# Schematic1.net
KiCad netlist of a schematic drawn in EAGLE
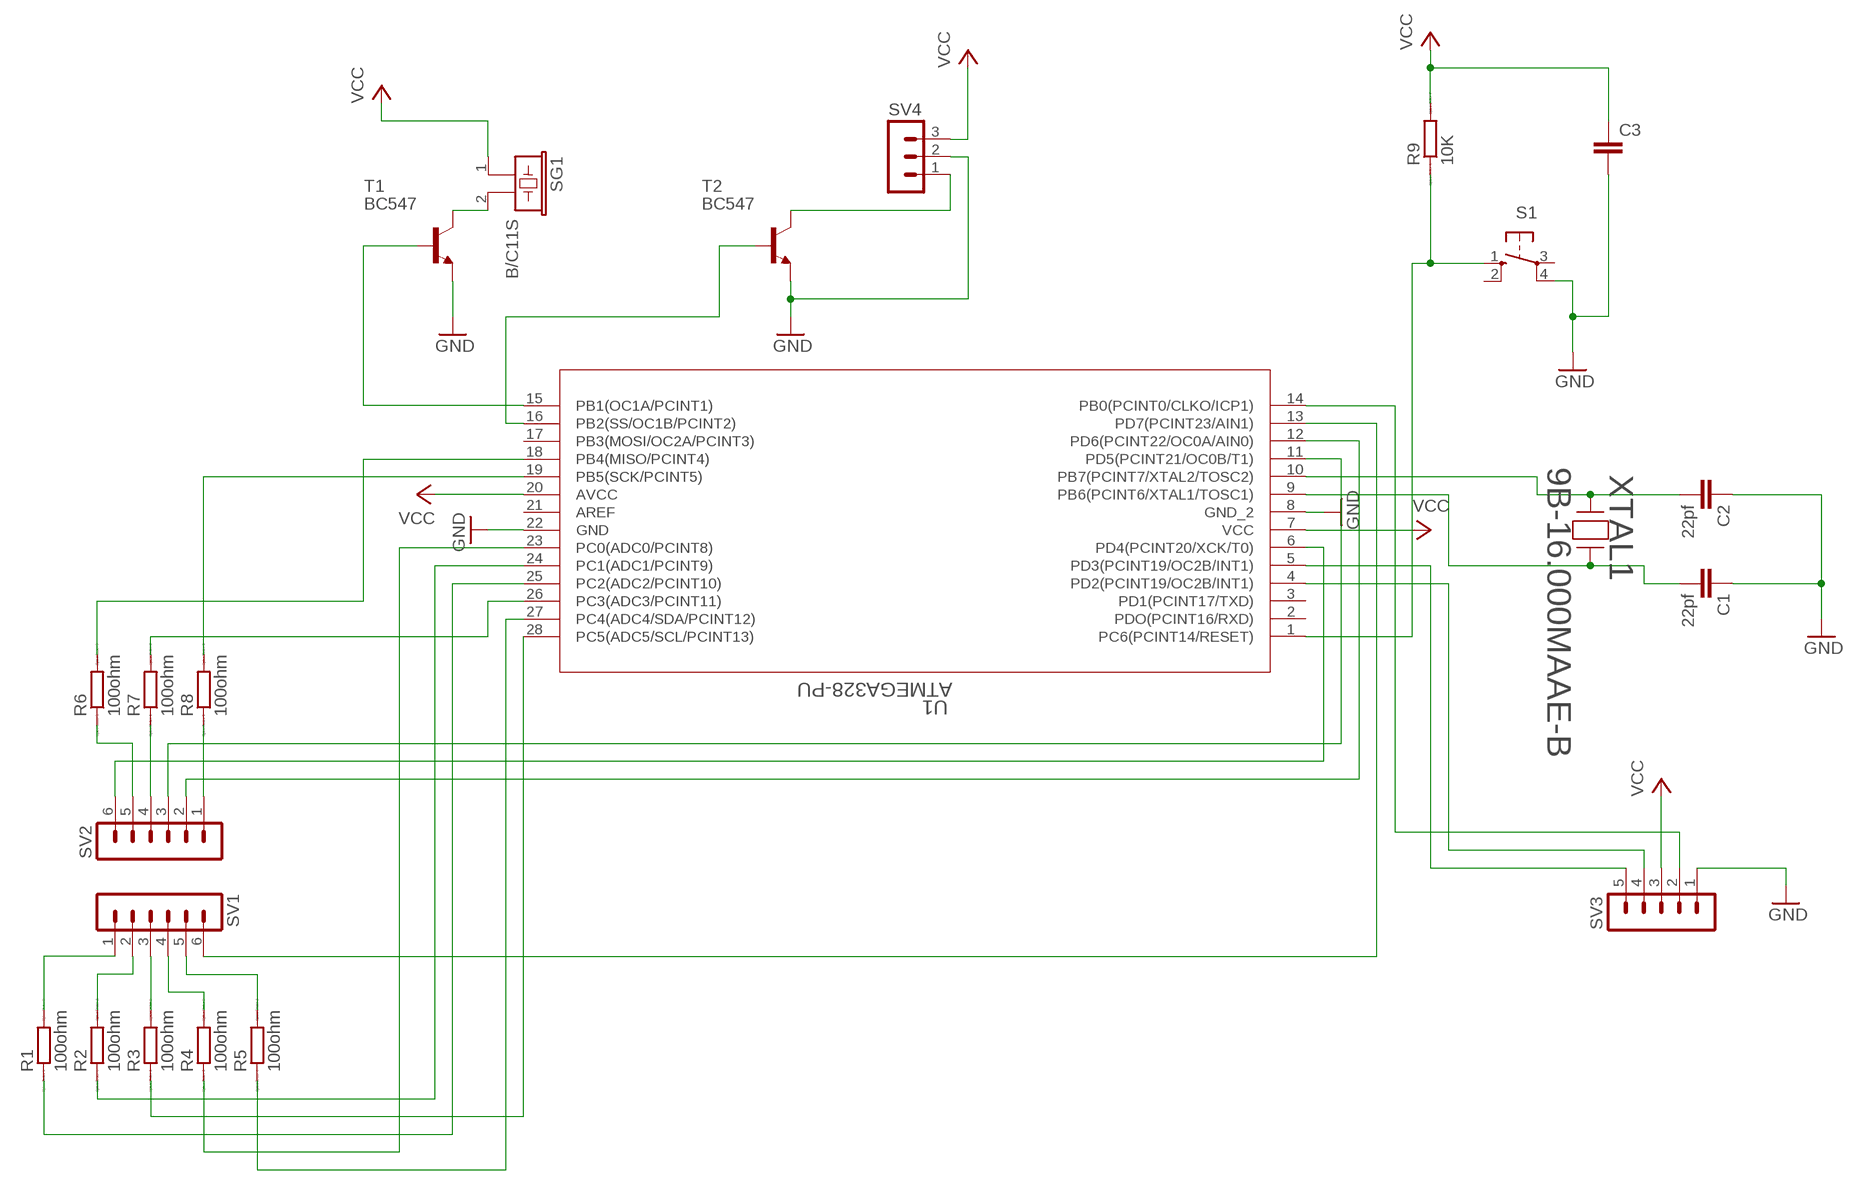
[diagram p0: schematic, sheet 1]

(export (version "E")
  (design (tool "Eeschema 10.0.6"))
  (components
    (comp (ref "C1")
      (value "22pf")
      (footprint "eagle-import:C2.5-3")
      (libsource (lib "eagle-import") (part "C2,5-3"))
    )
    (comp (ref "C2")
      (value "22pf")
      (footprint "eagle-import:C2.5-3")
      (libsource (lib "eagle-import") (part "C2,5-3"))
    )
    (comp (ref "C3")
      (value "C5/3")
      (footprint "eagle-import:C5B3")
      (libsource (lib "eagle-import") (part "C5/3"))
    )
    (comp (ref "R1")
      (value "100ohm")
      (footprint "eagle-import:0204_7")
      (libsource (lib "eagle-import") (part "R0204/7"))
    )
    (comp (ref "R2")
      (value "100ohm")
      (footprint "eagle-import:0204_7")
      (libsource (lib "eagle-import") (part "R0204/7"))
    )
    (comp (ref "R3")
      (value "100ohm")
      (footprint "eagle-import:0204_7")
      (libsource (lib "eagle-import") (part "R0204/7"))
    )
    (comp (ref "R4")
      (value "100ohm")
      (footprint "eagle-import:0204_7")
      (libsource (lib "eagle-import") (part "R0204/7"))
    )
    (comp (ref "R5")
      (value "100ohm")
      (footprint "eagle-import:0204_7")
      (libsource (lib "eagle-import") (part "R0204/7"))
    )
    (comp (ref "R6")
      (value "100ohm")
      (footprint "eagle-import:0204_7")
      (libsource (lib "eagle-import") (part "R0204/7"))
    )
    (comp (ref "R7")
      (value "100ohm")
      (footprint "eagle-import:0204_7")
      (libsource (lib "eagle-import") (part "R0204/7"))
    )
    (comp (ref "R8")
      (value "100ohm")
      (footprint "eagle-import:0204_7")
      (libsource (lib "eagle-import") (part "R0204/7"))
    )
    (comp (ref "R9")
      (value "10K")
      (footprint "eagle-import:0204_7")
      (libsource (lib "eagle-import") (part "R0204/7"))
    )
    (comp (ref "S1")
      (value "10-XX")
      (footprint "eagle-import:B3F-10XX")
      (fields (field (name "MPN") "B3F-1000"))
      (libsource (lib "eagle-import") (part "10-XX"))
    )
    (comp (ref "SG1")
      (value "B/C11S")
      (footprint "eagle-import:B_C11S")
      (libsource (lib "eagle-import") (part "B/C11S"))
    )
    (comp (ref "SV1")
      (value "MA06-1")
      (footprint "eagle-import:MA06-1")
      (libsource (lib "eagle-import") (part "MA06-1"))
    )
    (comp (ref "SV2")
      (value "MA06-1")
      (footprint "eagle-import:MA06-1")
      (libsource (lib "eagle-import") (part "MA06-1"))
    )
    (comp (ref "SV3")
      (value "MA05-1")
      (footprint "eagle-import:MA05-1")
      (libsource (lib "eagle-import") (part "MA05-1"))
    )
    (comp (ref "SV4")
      (value "MA03-1")
      (footprint "eagle-import:MA03-1")
      (libsource (lib "eagle-import") (part "MA03-1"))
    )
    (comp (ref "T1")
      (value "BC547")
      (footprint "eagle-import:TO92")
      (libsource (lib "eagle-import") (part "BC547"))
    )
    (comp (ref "T2")
      (value "BC547")
      (footprint "eagle-import:TO92")
      (libsource (lib "eagle-import") (part "BC547"))
    )
    (comp (ref "U1")
      (value "ATMEGA328-PU")
      (footprint "eagle-import:28P3_SPDIP28_SP_MCH")
      (fields (field (name "COPYRIGHT") "Copyright (C) 2023 Ultra Librarian. All rights reserved."))
      (libsource (lib "eagle-import") (part "ATMEGA328-PU"))
    )
    (comp (ref "XTAL1")
      (value "9B-16.000MAAE-B")
      (footprint "eagle-import:9B-16.000MAAE-B_TXC")
      (fields (field (name "COPYRIGHT") "Copyright (C) 2023 Ultra Librarian. All rights reserved."))
      (libsource (lib "eagle-import") (part "9B-16.000MAAE-B"))
    )
  )
  (nets
    (net (code "1") (name "GND") (class "Default")
      (node (ref "C1") (pin "1") (pinfunction "1_1") (pintype "passive"))
      (node (ref "C2") (pin "1") (pinfunction "1_1") (pintype "passive"))
      (node (ref "C3") (pin "2") (pinfunction "2_2") (pintype "passive"))
      (node (ref "S1") (pin "4") (pinfunction "P1_4") (pintype "passive"))
      (node (ref "SV3") (pin "1") (pinfunction "1_1") (pintype "passive"))
      (node (ref "SV4") (pin "2") (pinfunction "2_2") (pintype "passive"))
      (node (ref "T1") (pin "1") (pinfunction "E_1") (pintype "passive"))
      (node (ref "T2") (pin "1") (pinfunction "E_1") (pintype "passive"))
      (node (ref "U1") (pin "22") (pinfunction "GND_22") (pintype "passive"))
      (node (ref "U1") (pin "8") (pinfunction "GND_2_8") (pintype "passive"))
    )
    (net (code "2") (name "Net-(R1-Pad2)") (class "Default")
      (node (ref "R1") (pin "2") (pinfunction "2_2") (pintype "passive"))
      (node (ref "SV1") (pin "1") (pinfunction "1_1") (pintype "passive"))
    )
    (net (code "3") (name "Net-(R2-Pad2)") (class "Default")
      (node (ref "R2") (pin "2") (pinfunction "2_2") (pintype "passive"))
      (node (ref "SV1") (pin "2") (pinfunction "2_2") (pintype "passive"))
    )
    (net (code "4") (name "Net-(R3-Pad2)") (class "Default")
      (node (ref "R3") (pin "2") (pinfunction "2_2") (pintype "passive"))
      (node (ref "SV1") (pin "3") (pinfunction "3_3") (pintype "passive"))
    )
    (net (code "5") (name "Net-(R4-Pad2)") (class "Default")
      (node (ref "R4") (pin "2") (pinfunction "2_2") (pintype "passive"))
      (node (ref "SV1") (pin "4") (pinfunction "4_4") (pintype "passive"))
    )
    (net (code "6") (name "Net-(R5-Pad2)") (class "Default")
      (node (ref "R5") (pin "2") (pinfunction "2_2") (pintype "passive"))
      (node (ref "SV1") (pin "5") (pinfunction "5_5") (pintype "passive"))
    )
    (net (code "7") (name "Net-(R6-Pad1)") (class "Default")
      (node (ref "R6") (pin "1") (pinfunction "1_1") (pintype "passive"))
      (node (ref "SV2") (pin "5") (pinfunction "5_5") (pintype "passive"))
    )
    (net (code "8") (name "Net-(R7-Pad1)") (class "Default")
      (node (ref "R7") (pin "1") (pinfunction "1_1") (pintype "passive"))
      (node (ref "SV2") (pin "4") (pinfunction "4_4") (pintype "passive"))
    )
    (net (code "9") (name "Net-(R8-Pad1)") (class "Default")
      (node (ref "R8") (pin "1") (pinfunction "1_1") (pintype "passive"))
      (node (ref "SV2") (pin "1") (pinfunction "1_1") (pintype "passive"))
    )
    (net (code "10") (name "Net-(S1-S)") (class "Default")
      (node (ref "R9") (pin "1") (pinfunction "1_1") (pintype "passive"))
      (node (ref "S1") (pin "1") (pinfunction "S_1") (pintype "passive"))
      (node (ref "U1") (pin "1") (pinfunction "PC6(PCINT14/RESET)_1") (pintype "bidirectional"))
    )
    (net (code "11") (name "Net-(T1-B)") (class "Default")
      (node (ref "T1") (pin "2") (pinfunction "B_2") (pintype "passive"))
      (node (ref "U1") (pin "15") (pinfunction "PB1(OC1A/PCINT1)_15") (pintype "bidirectional"))
    )
    (net (code "12") (name "Net-(T1-C)") (class "Default")
      (node (ref "SG1") (pin "2") (pinfunction "2_2") (pintype "passive"))
      (node (ref "T1") (pin "3") (pinfunction "C_3") (pintype "passive"))
    )
    (net (code "13") (name "Net-(T2-B)") (class "Default")
      (node (ref "T2") (pin "2") (pinfunction "B_2") (pintype "passive"))
      (node (ref "U1") (pin "16") (pinfunction "PB2(SS/OC1B/PCINT2)_16") (pintype "bidirectional"))
    )
    (net (code "14") (name "Net-(T2-C)") (class "Default")
      (node (ref "SV4") (pin "1") (pinfunction "1_1") (pintype "passive"))
      (node (ref "T2") (pin "3") (pinfunction "C_3") (pintype "passive"))
    )
    (net (code "15") (name "Net-(U1-PB0(PCINT0{slash}CLKO{slash}ICP1))") (class "Default")
      (node (ref "SV3") (pin "2") (pinfunction "2_2") (pintype "passive"))
      (node (ref "SV3") (pin "5") (pinfunction "5_5") (pintype "passive"))
      (node (ref "U1") (pin "14") (pinfunction "PB0(PCINT0/CLKO/ICP1)_14") (pintype "bidirectional"))
      (node (ref "U1") (pin "5") (pinfunction "PD3(PCINT19/OC2B/INT1)_5") (pintype "bidirectional"))
    )
    (net (code "16") (name "Net-(U1-PB4(MISO{slash}PCINT4))") (class "Default")
      (node (ref "R6") (pin "2") (pinfunction "2_2") (pintype "passive"))
      (node (ref "U1") (pin "18") (pinfunction "PB4(MISO/PCINT4)_18") (pintype "bidirectional"))
    )
    (net (code "17") (name "Net-(U1-PB5(SCK{slash}PCINT5))") (class "Default")
      (node (ref "R8") (pin "2") (pinfunction "2_2") (pintype "passive"))
      (node (ref "U1") (pin "19") (pinfunction "PB5(SCK/PCINT5)_19") (pintype "bidirectional"))
    )
    (net (code "18") (name "Net-(U1-PB6(PCINT6{slash}XTAL1{slash}TOSC1))") (class "Default")
      (node (ref "C1") (pin "2") (pinfunction "2_2") (pintype "passive"))
      (node (ref "U1") (pin "9") (pinfunction "PB6(PCINT6/XTAL1/TOSC1)_9") (pintype "bidirectional"))
      (node (ref "XTAL1") (pin "2") (pinfunction "2_2") (pintype "passive"))
    )
    (net (code "19") (name "Net-(U1-PB7(PCINT7{slash}XTAL2{slash}TOSC2))") (class "Default")
      (node (ref "C2") (pin "2") (pinfunction "2_2") (pintype "passive"))
      (node (ref "U1") (pin "10") (pinfunction "PB7(PCINT7/XTAL2/TOSC2)_10") (pintype "bidirectional"))
      (node (ref "XTAL1") (pin "1") (pinfunction "1_1") (pintype "passive"))
    )
    (net (code "20") (name "Net-(U1-PC0(ADC0{slash}PCINT8))") (class "Default")
      (node (ref "R4") (pin "1") (pinfunction "1_1") (pintype "passive"))
      (node (ref "U1") (pin "23") (pinfunction "PC0(ADC0/PCINT8)_23") (pintype "bidirectional"))
    )
    (net (code "21") (name "Net-(U1-PC1(ADC1{slash}PCINT9))") (class "Default")
      (node (ref "R2") (pin "1") (pinfunction "1_1") (pintype "passive"))
      (node (ref "U1") (pin "24") (pinfunction "PC1(ADC1/PCINT9)_24") (pintype "bidirectional"))
    )
    (net (code "22") (name "Net-(U1-PC2(ADC2{slash}PCINT10))") (class "Default")
      (node (ref "R1") (pin "1") (pinfunction "1_1") (pintype "passive"))
      (node (ref "U1") (pin "25") (pinfunction "PC2(ADC2/PCINT10)_25") (pintype "bidirectional"))
    )
    (net (code "23") (name "Net-(U1-PC3(ADC3{slash}PCINT11))") (class "Default")
      (node (ref "R7") (pin "2") (pinfunction "2_2") (pintype "passive"))
      (node (ref "U1") (pin "26") (pinfunction "PC3(ADC3/PCINT11)_26") (pintype "bidirectional"))
    )
    (net (code "24") (name "Net-(U1-PC4(ADC4{slash}SDA{slash}PCINT12))") (class "Default")
      (node (ref "R5") (pin "1") (pinfunction "1_1") (pintype "passive"))
      (node (ref "U1") (pin "27") (pinfunction "PC4(ADC4/SDA/PCINT12)_27") (pintype "bidirectional"))
    )
    (net (code "25") (name "Net-(U1-PC5(ADC5{slash}SCL{slash}PCINT13))") (class "Default")
      (node (ref "R3") (pin "1") (pinfunction "1_1") (pintype "passive"))
      (node (ref "U1") (pin "28") (pinfunction "PC5(ADC5/SCL/PCINT13)_28") (pintype "bidirectional"))
    )
    (net (code "26") (name "Net-(U1-PD2(PCINT19{slash}OC2B{slash}INT1))") (class "Default")
      (node (ref "SV3") (pin "4") (pinfunction "4_4") (pintype "passive"))
      (node (ref "U1") (pin "4") (pinfunction "PD2(PCINT19/OC2B/INT1)_4") (pintype "bidirectional"))
    )
    (net (code "27") (name "Net-(U1-PD4(PCINT20{slash}XCK{slash}T0))") (class "Default")
      (node (ref "SV2") (pin "6") (pinfunction "6_6") (pintype "passive"))
      (node (ref "U1") (pin "6") (pinfunction "PD4(PCINT20/XCK/T0)_6") (pintype "bidirectional"))
    )
    (net (code "28") (name "Net-(U1-PD5(PCINT21{slash}OC0B{slash}T1))") (class "Default")
      (node (ref "SV2") (pin "3") (pinfunction "3_3") (pintype "passive"))
      (node (ref "U1") (pin "11") (pinfunction "PD5(PCINT21/OC0B/T1)_11") (pintype "bidirectional"))
    )
    (net (code "29") (name "Net-(U1-PD6(PCINT22{slash}OC0A{slash}AIN0))") (class "Default")
      (node (ref "SV2") (pin "2") (pinfunction "2_2") (pintype "passive"))
      (node (ref "U1") (pin "12") (pinfunction "PD6(PCINT22/OC0A/AIN0)_12") (pintype "bidirectional"))
    )
    (net (code "30") (name "Net-(U1-PD7(PCINT23{slash}AIN1))") (class "Default")
      (node (ref "SV1") (pin "6") (pinfunction "6_6") (pintype "passive"))
      (node (ref "U1") (pin "13") (pinfunction "PD7(PCINT23/AIN1)_13") (pintype "bidirectional"))
    )
    (net (code "31") (name "VCC") (class "Default")
      (node (ref "C3") (pin "1") (pinfunction "1_1") (pintype "passive"))
      (node (ref "R9") (pin "2") (pinfunction "2_2") (pintype "passive"))
      (node (ref "SG1") (pin "1") (pinfunction "1_1") (pintype "passive"))
      (node (ref "SV3") (pin "3") (pinfunction "3_3") (pintype "passive"))
      (node (ref "SV4") (pin "3") (pinfunction "3_3") (pintype "passive"))
      (node (ref "U1") (pin "20") (pinfunction "AVCC_20") (pintype "power_in"))
      (node (ref "U1") (pin "7") (pinfunction "VCC_7") (pintype "power_in"))
    )
    (net (code "32") (name "unconnected-(S1-P-Pad3)") (class "Default")
      (node (ref "S1") (pin "3") (pinfunction "P_3") (pintype "passive"))
    )
    (net (code "33") (name "unconnected-(S1-S1-Pad2)") (class "Default")
      (node (ref "S1") (pin "2") (pinfunction "S1_2") (pintype "passive"))
    )
    (net (code "34") (name "unconnected-(U1-AREF-Pad21)") (class "Default")
      (node (ref "U1") (pin "21") (pinfunction "AREF_21") (pintype "passive"))
    )
    (net (code "35") (name "unconnected-(U1-PB3(MOSI{slash}OC2A{slash}PCINT3)-Pad17)") (class "Default")
      (node (ref "U1") (pin "17") (pinfunction "PB3(MOSI/OC2A/PCINT3)_17") (pintype "bidirectional"))
    )
    (net (code "36") (name "unconnected-(U1-PD1(PCINT17{slash}TXD)-Pad3)") (class "Default")
      (node (ref "U1") (pin "3") (pinfunction "PD1(PCINT17/TXD)_3") (pintype "bidirectional"))
    )
    (net (code "37") (name "unconnected-(U1-PDO(PCINT16{slash}RXD)-Pad2)") (class "Default")
      (node (ref "U1") (pin "2") (pinfunction "PDO(PCINT16/RXD)_2") (pintype "bidirectional"))
    )
  )
)
